# ADC-Z-DOK.net
KiCad netlist of a schematic drawn in Altium Designer
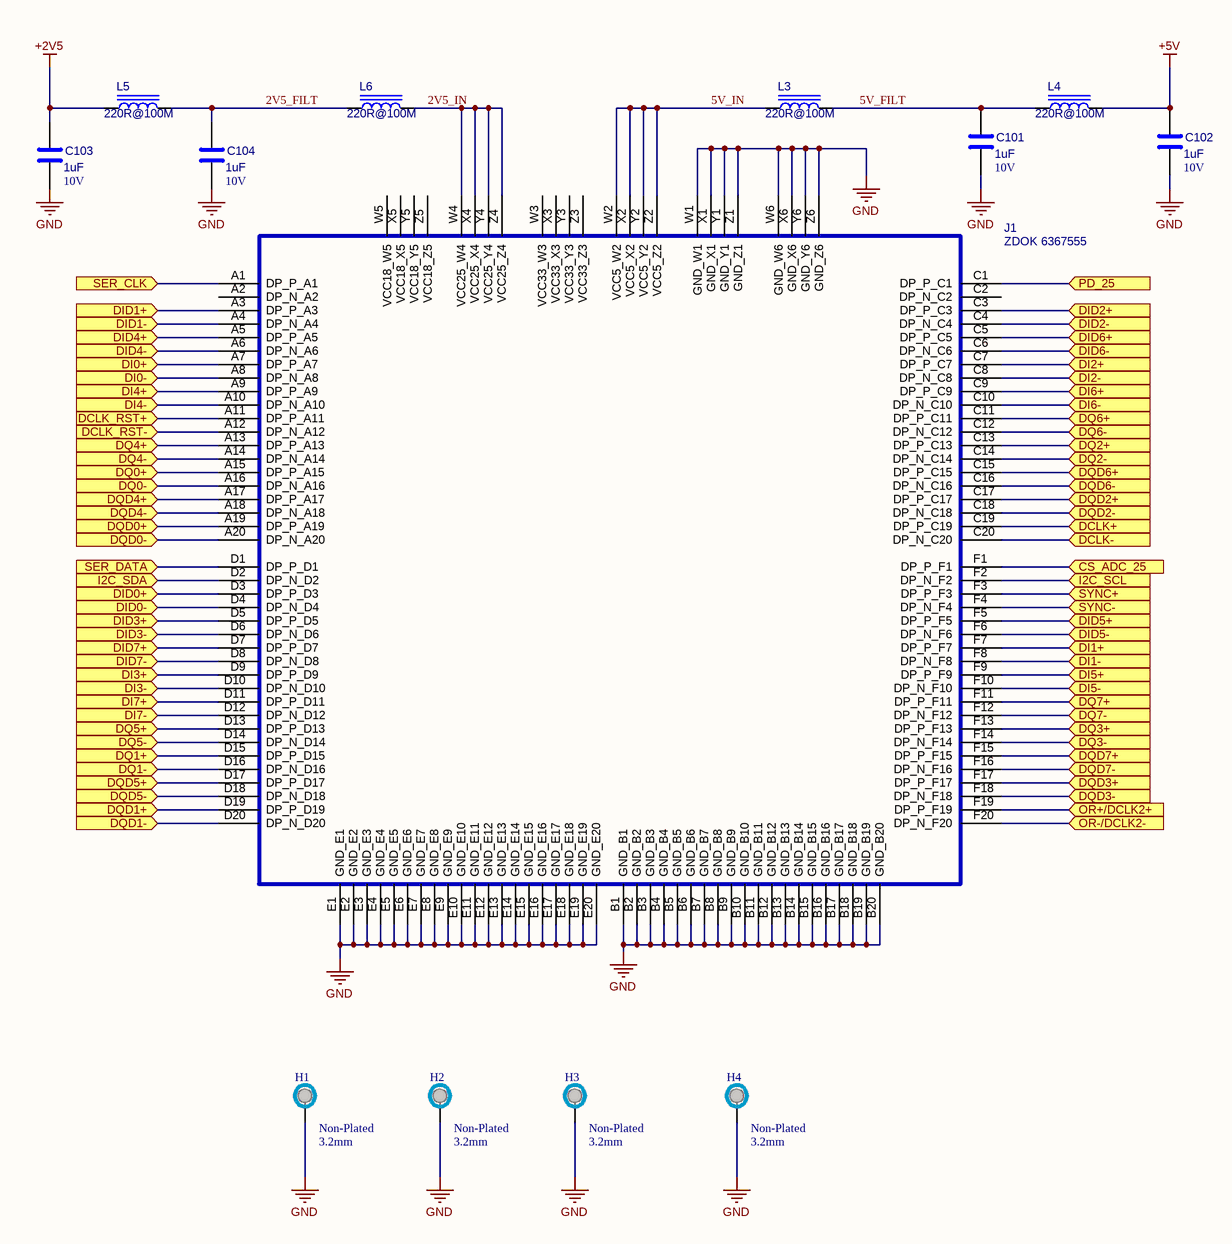
[diagram p0: ADC-Z-DOK.SchDoc]

(export (version "E")
  (design (tool "Eeschema 10.0.6"))
  (components
    (comp (ref "C101")
      (value "1uF")
      (footprint "CAPC1632X80USR")
      (description "CAP SMD 0603")
      (fields (field (name "VOLTAGE") "10V") (field (name "CREATED_BY") "*") (field (name "CHECKED_BY") "*"))
      (libsource (lib "Abdus-TEMP") (part "CAP-0603"))
    )
    (comp (ref "C102")
      (value "1uF")
      (footprint "CAPC1632X80USR")
      (description "CAP SMD 0603")
      (fields (field (name "VOLTAGE") "10V") (field (name "CREATED_BY") "*") (field (name "CHECKED_BY") "*"))
      (libsource (lib "Abdus-TEMP") (part "CAP-0603"))
    )
    (comp (ref "C103")
      (value "1uF")
      (footprint "CAPC1632X80USR")
      (description "CAP SMD 0603")
      (fields (field (name "VOLTAGE") "10V") (field (name "CREATED_BY") "*") (field (name "CHECKED_BY") "*"))
      (libsource (lib "Abdus-TEMP") (part "CAP-0603"))
    )
    (comp (ref "C104")
      (value "1uF")
      (footprint "CAPC1632X80USR")
      (description "CAP SMD 0603")
      (fields (field (name "VOLTAGE") "10V") (field (name "CREATED_BY") "*") (field (name "CHECKED_BY") "*"))
      (libsource (lib "Abdus-TEMP") (part "CAP-0603"))
    )
    (comp (ref "H1")
      (value "Non-Plated")
      (footprint "HOLE")
      (description "PCB Mounting Hole")
      (fields (field (name "HOLEDIA") "3.2mm"))
      (libsource (lib "Analog_Outputs") (part "Unplated Hole_3.2mm"))
    )
    (comp (ref "H2")
      (value "Non-Plated")
      (footprint "HOLE")
      (description "PCB Mounting Hole")
      (fields (field (name "HOLEDIA") "3.2mm"))
      (libsource (lib "Analog_Outputs") (part "Unplated Hole_3.2mm"))
    )
    (comp (ref "H3")
      (value "Non-Plated")
      (footprint "HOLE")
      (description "PCB Mounting Hole")
      (fields (field (name "HOLEDIA") "3.2mm"))
      (libsource (lib "Analog_Outputs") (part "Unplated Hole_3.2mm"))
    )
    (comp (ref "H4")
      (value "Non-Plated")
      (footprint "HOLE")
      (description "PCB Mounting Hole")
      (fields (field (name "HOLEDIA") "3.2mm"))
      (libsource (lib "Analog_Outputs") (part "Unplated Hole_3.2mm"))
    )
    (comp (ref "J1")
      (value "Z-DOK")
      (footprint "TYCO6367555")
      (fields
        (field (name "MANUFACTURER_PN") "ZDOK 6367555")
        (field (name "CREATED_BY") "CT")
        (field (name "CHECKED_BY") "*")
      )
      (libsource (lib "Charles-TEMP") (part "ZDOK 6367555"))
    )
    (comp (ref "L3")
      (value "TDK")
      (footprint "INDC1608X80USR")
      (description "POWER LINE")
      (fields
        (field (name "VOLTAGE") "220R@100M")
        (field (name "CREATED_BY") "*")
        (field (name "CHECKED_BY") "*")
      )
      (libsource (lib "Charles-TEMP") (part "MPZ16085221A"))
    )
    (comp (ref "L4")
      (value "TDK")
      (footprint "INDC1608X80USR")
      (description "POWER LINE")
      (fields
        (field (name "VOLTAGE") "220R@100M")
        (field (name "CREATED_BY") "*")
        (field (name "CHECKED_BY") "*")
      )
      (libsource (lib "Charles-TEMP") (part "MPZ16085221A"))
    )
    (comp (ref "L5")
      (value "TDK")
      (footprint "INDC1608X80USR")
      (description "POWER LINE")
      (fields
        (field (name "VOLTAGE") "220R@100M")
        (field (name "CREATED_BY") "*")
        (field (name "CHECKED_BY") "*")
      )
      (libsource (lib "Charles-TEMP") (part "MPZ16085221A"))
    )
    (comp (ref "L6")
      (value "TDK")
      (footprint "INDC1608X80USR")
      (description "POWER LINE")
      (fields
        (field (name "VOLTAGE") "220R@100M")
        (field (name "CREATED_BY") "*")
        (field (name "CHECKED_BY") "*")
      )
      (libsource (lib "Charles-TEMP") (part "MPZ16085221A"))
    )
  )
  (nets
    (net (code "1") (name "+2V5") (class "Default")
      (node (ref "C103") (pin "1") (pinfunction "1_1") (pintype "passive"))
      (node (ref "L5") (pin "1") (pinfunction "1_1") (pintype "passive"))
    )
    (net (code "2") (name "+5V") (class "Default")
      (node (ref "C102") (pin "1") (pinfunction "1_1") (pintype "passive"))
      (node (ref "L4") (pin "2") (pinfunction "2_2") (pintype "passive"))
    )
    (net (code "3") (name "/2V5_FILT") (class "Default")
      (node (ref "C104") (pin "1") (pinfunction "1_1") (pintype "passive"))
      (node (ref "L5") (pin "2") (pinfunction "2_2") (pintype "passive"))
      (node (ref "L6") (pin "1") (pinfunction "1_1") (pintype "passive"))
    )
    (net (code "4") (name "/2V5_IN") (class "Default")
      (node (ref "J1") (pin "W4") (pinfunction "VCC25_W4_W4") (pintype "power_in"))
      (node (ref "J1") (pin "X4") (pinfunction "VCC25_X4_X4") (pintype "power_in"))
      (node (ref "J1") (pin "Y4") (pinfunction "VCC25_Y4_Y4") (pintype "power_in"))
      (node (ref "J1") (pin "Z4") (pinfunction "VCC25_Z4_Z4") (pintype "power_in"))
      (node (ref "L6") (pin "2") (pinfunction "2_2") (pintype "passive"))
    )
    (net (code "5") (name "/5V_FILT") (class "Default")
      (node (ref "C101") (pin "1") (pinfunction "1_1") (pintype "passive"))
      (node (ref "L3") (pin "2") (pinfunction "2_2") (pintype "passive"))
      (node (ref "L4") (pin "1") (pinfunction "1_1") (pintype "passive"))
    )
    (net (code "6") (name "/5V_IN") (class "Default")
      (node (ref "J1") (pin "W2") (pinfunction "VCC5_W2_W2") (pintype "power_in"))
      (node (ref "J1") (pin "X2") (pinfunction "VCC5_X2_X2") (pintype "power_in"))
      (node (ref "J1") (pin "Y2") (pinfunction "VCC5_Y2_Y2") (pintype "power_in"))
      (node (ref "J1") (pin "Z2") (pinfunction "VCC5_Z2_Z2") (pintype "power_in"))
      (node (ref "L3") (pin "1") (pinfunction "1_1") (pintype "passive"))
    )
    (net (code "7") (name "/CS_ADC_25") (class "Default")
      (node (ref "J1") (pin "F1") (pinfunction "DP_P_F1_F1") (pintype "passive"))
    )
    (net (code "8") (name "/DCLK+") (class "Default")
      (node (ref "J1") (pin "C19") (pinfunction "DP_P_C19_C19") (pintype "passive"))
    )
    (net (code "9") (name "/DCLK-") (class "Default")
      (node (ref "J1") (pin "C20") (pinfunction "DP_N_C20_C20") (pintype "passive"))
    )
    (net (code "10") (name "/DCLK_RST+") (class "Default")
      (node (ref "J1") (pin "A11") (pinfunction "DP_P_A11_A11") (pintype "passive"))
    )
    (net (code "11") (name "/DCLK_RST-") (class "Default")
      (node (ref "J1") (pin "A12") (pinfunction "DP_N_A12_A12") (pintype "passive"))
    )
    (net (code "12") (name "/DI0+") (class "Default")
      (node (ref "J1") (pin "A7") (pinfunction "DP_P_A7_A7") (pintype "passive"))
    )
    (net (code "13") (name "/DI0-") (class "Default")
      (node (ref "J1") (pin "A8") (pinfunction "DP_N_A8_A8") (pintype "passive"))
    )
    (net (code "14") (name "/DI1+") (class "Default")
      (node (ref "J1") (pin "F7") (pinfunction "DP_P_F7_F7") (pintype "passive"))
    )
    (net (code "15") (name "/DI1-") (class "Default")
      (node (ref "J1") (pin "F8") (pinfunction "DP_N_F8_F8") (pintype "passive"))
    )
    (net (code "16") (name "/DI2+") (class "Default")
      (node (ref "J1") (pin "C7") (pinfunction "DP_P_C7_C7") (pintype "passive"))
    )
    (net (code "17") (name "/DI2-") (class "Default")
      (node (ref "J1") (pin "C8") (pinfunction "DP_N_C8_C8") (pintype "passive"))
    )
    (net (code "18") (name "/DI3+") (class "Default")
      (node (ref "J1") (pin "D9") (pinfunction "DP_P_D9_D9") (pintype "passive"))
    )
    (net (code "19") (name "/DI3-") (class "Default")
      (node (ref "J1") (pin "D10") (pinfunction "DP_N_D10_D10") (pintype "passive"))
    )
    (net (code "20") (name "/DI4+") (class "Default")
      (node (ref "J1") (pin "A9") (pinfunction "DP_P_A9_A9") (pintype "passive"))
    )
    (net (code "21") (name "/DI4-") (class "Default")
      (node (ref "J1") (pin "A10") (pinfunction "DP_N_A10_A10") (pintype "passive"))
    )
    (net (code "22") (name "/DI5+") (class "Default")
      (node (ref "J1") (pin "F9") (pinfunction "DP_P_F9_F9") (pintype "passive"))
    )
    (net (code "23") (name "/DI5-") (class "Default")
      (node (ref "J1") (pin "F10") (pinfunction "DP_N_F10_F10") (pintype "passive"))
    )
    (net (code "24") (name "/DI6+") (class "Default")
      (node (ref "J1") (pin "C9") (pinfunction "DP_P_C9_C9") (pintype "passive"))
    )
    (net (code "25") (name "/DI6-") (class "Default")
      (node (ref "J1") (pin "C10") (pinfunction "DP_N_C10_C10") (pintype "passive"))
    )
    (net (code "26") (name "/DI7+") (class "Default")
      (node (ref "J1") (pin "D11") (pinfunction "DP_P_D11_D11") (pintype "passive"))
    )
    (net (code "27") (name "/DI7-") (class "Default")
      (node (ref "J1") (pin "D12") (pinfunction "DP_N_D12_D12") (pintype "passive"))
    )
    (net (code "28") (name "/DID0+") (class "Default")
      (node (ref "J1") (pin "D3") (pinfunction "DP_P_D3_D3") (pintype "passive"))
    )
    (net (code "29") (name "/DID0-") (class "Default")
      (node (ref "J1") (pin "D4") (pinfunction "DP_N_D4_D4") (pintype "passive"))
    )
    (net (code "30") (name "/DID1+") (class "Default")
      (node (ref "J1") (pin "A3") (pinfunction "DP_P_A3_A3") (pintype "passive"))
    )
    (net (code "31") (name "/DID1-") (class "Default")
      (node (ref "J1") (pin "A4") (pinfunction "DP_N_A4_A4") (pintype "passive"))
    )
    (net (code "32") (name "/DID2+") (class "Default")
      (node (ref "J1") (pin "C3") (pinfunction "DP_P_C3_C3") (pintype "passive"))
    )
    (net (code "33") (name "/DID2-") (class "Default")
      (node (ref "J1") (pin "C4") (pinfunction "DP_N_C4_C4") (pintype "passive"))
    )
    (net (code "34") (name "/DID3+") (class "Default")
      (node (ref "J1") (pin "D5") (pinfunction "DP_P_D5_D5") (pintype "passive"))
    )
    (net (code "35") (name "/DID3-") (class "Default")
      (node (ref "J1") (pin "D6") (pinfunction "DP_N_D6_D6") (pintype "passive"))
    )
    (net (code "36") (name "/DID4+") (class "Default")
      (node (ref "J1") (pin "A5") (pinfunction "DP_P_A5_A5") (pintype "passive"))
    )
    (net (code "37") (name "/DID4-") (class "Default")
      (node (ref "J1") (pin "A6") (pinfunction "DP_N_A6_A6") (pintype "passive"))
    )
    (net (code "38") (name "/DID5+") (class "Default")
      (node (ref "J1") (pin "F5") (pinfunction "DP_P_F5_F5") (pintype "passive"))
    )
    (net (code "39") (name "/DID5-") (class "Default")
      (node (ref "J1") (pin "F6") (pinfunction "DP_N_F6_F6") (pintype "passive"))
    )
    (net (code "40") (name "/DID6+") (class "Default")
      (node (ref "J1") (pin "C5") (pinfunction "DP_P_C5_C5") (pintype "passive"))
    )
    (net (code "41") (name "/DID6-") (class "Default")
      (node (ref "J1") (pin "C6") (pinfunction "DP_N_C6_C6") (pintype "passive"))
    )
    (net (code "42") (name "/DID7+") (class "Default")
      (node (ref "J1") (pin "D7") (pinfunction "DP_P_D7_D7") (pintype "passive"))
    )
    (net (code "43") (name "/DID7-") (class "Default")
      (node (ref "J1") (pin "D8") (pinfunction "DP_N_D8_D8") (pintype "passive"))
    )
    (net (code "44") (name "/DQ0+") (class "Default")
      (node (ref "J1") (pin "A15") (pinfunction "DP_P_A15_A15") (pintype "passive"))
    )
    (net (code "45") (name "/DQ0-") (class "Default")
      (node (ref "J1") (pin "A16") (pinfunction "DP_N_A16_A16") (pintype "passive"))
    )
    (net (code "46") (name "/DQ1+") (class "Default")
      (node (ref "J1") (pin "D15") (pinfunction "DP_P_D15_D15") (pintype "passive"))
    )
    (net (code "47") (name "/DQ1-") (class "Default")
      (node (ref "J1") (pin "D16") (pinfunction "DP_N_D16_D16") (pintype "passive"))
    )
    (net (code "48") (name "/DQ2+") (class "Default")
      (node (ref "J1") (pin "C13") (pinfunction "DP_P_C13_C13") (pintype "passive"))
    )
    (net (code "49") (name "/DQ2-") (class "Default")
      (node (ref "J1") (pin "C14") (pinfunction "DP_N_C14_C14") (pintype "passive"))
    )
    (net (code "50") (name "/DQ3+") (class "Default")
      (node (ref "J1") (pin "F13") (pinfunction "DP_P_F13_F13") (pintype "passive"))
    )
    (net (code "51") (name "/DQ3-") (class "Default")
      (node (ref "J1") (pin "F14") (pinfunction "DP_N_F14_F14") (pintype "passive"))
    )
    (net (code "52") (name "/DQ4+") (class "Default")
      (node (ref "J1") (pin "A13") (pinfunction "DP_P_A13_A13") (pintype "passive"))
    )
    (net (code "53") (name "/DQ4-") (class "Default")
      (node (ref "J1") (pin "A14") (pinfunction "DP_N_A14_A14") (pintype "passive"))
    )
    (net (code "54") (name "/DQ5+") (class "Default")
      (node (ref "J1") (pin "D13") (pinfunction "DP_P_D13_D13") (pintype "passive"))
    )
    (net (code "55") (name "/DQ5-") (class "Default")
      (node (ref "J1") (pin "D14") (pinfunction "DP_N_D14_D14") (pintype "passive"))
    )
    (net (code "56") (name "/DQ6+") (class "Default")
      (node (ref "J1") (pin "C11") (pinfunction "DP_P_C11_C11") (pintype "passive"))
    )
    (net (code "57") (name "/DQ6-") (class "Default")
      (node (ref "J1") (pin "C12") (pinfunction "DP_N_C12_C12") (pintype "passive"))
    )
    (net (code "58") (name "/DQ7+") (class "Default")
      (node (ref "J1") (pin "F11") (pinfunction "DP_P_F11_F11") (pintype "passive"))
    )
    (net (code "59") (name "/DQ7-") (class "Default")
      (node (ref "J1") (pin "F12") (pinfunction "DP_N_F12_F12") (pintype "passive"))
    )
    (net (code "60") (name "/DQD0+") (class "Default")
      (node (ref "J1") (pin "A19") (pinfunction "DP_P_A19_A19") (pintype "passive"))
    )
    (net (code "61") (name "/DQD0-") (class "Default")
      (node (ref "J1") (pin "A20") (pinfunction "DP_N_A20_A20") (pintype "passive"))
    )
    (net (code "62") (name "/DQD1+") (class "Default")
      (node (ref "J1") (pin "D19") (pinfunction "DP_P_D19_D19") (pintype "passive"))
    )
    (net (code "63") (name "/DQD1-") (class "Default")
      (node (ref "J1") (pin "D20") (pinfunction "DP_N_D20_D20") (pintype "passive"))
    )
    (net (code "64") (name "/DQD2+") (class "Default")
      (node (ref "J1") (pin "C17") (pinfunction "DP_P_C17_C17") (pintype "passive"))
    )
    (net (code "65") (name "/DQD2-") (class "Default")
      (node (ref "J1") (pin "C18") (pinfunction "DP_N_C18_C18") (pintype "passive"))
    )
    (net (code "66") (name "/DQD3+") (class "Default")
      (node (ref "J1") (pin "F17") (pinfunction "DP_P_F17_F17") (pintype "passive"))
    )
    (net (code "67") (name "/DQD3-") (class "Default")
      (node (ref "J1") (pin "F18") (pinfunction "DP_N_F18_F18") (pintype "passive"))
    )
    (net (code "68") (name "/DQD4+") (class "Default")
      (node (ref "J1") (pin "A17") (pinfunction "DP_P_A17_A17") (pintype "passive"))
    )
    (net (code "69") (name "/DQD4-") (class "Default")
      (node (ref "J1") (pin "A18") (pinfunction "DP_N_A18_A18") (pintype "passive"))
    )
    (net (code "70") (name "/DQD5+") (class "Default")
      (node (ref "J1") (pin "D17") (pinfunction "DP_P_D17_D17") (pintype "passive"))
    )
    (net (code "71") (name "/DQD5-") (class "Default")
      (node (ref "J1") (pin "D18") (pinfunction "DP_N_D18_D18") (pintype "passive"))
    )
    (net (code "72") (name "/DQD6+") (class "Default")
      (node (ref "J1") (pin "C15") (pinfunction "DP_P_C15_C15") (pintype "passive"))
    )
    (net (code "73") (name "/DQD6-") (class "Default")
      (node (ref "J1") (pin "C16") (pinfunction "DP_N_C16_C16") (pintype "passive"))
    )
    (net (code "74") (name "/DQD7+") (class "Default")
      (node (ref "J1") (pin "F15") (pinfunction "DP_P_F15_F15") (pintype "passive"))
    )
    (net (code "75") (name "/DQD7-") (class "Default")
      (node (ref "J1") (pin "F16") (pinfunction "DP_N_F16_F16") (pintype "passive"))
    )
    (net (code "76") (name "/I2C_SCL") (class "Default")
      (node (ref "J1") (pin "F2") (pinfunction "DP_N_F2_F2") (pintype "passive"))
    )
    (net (code "77") (name "/I2C_SDA") (class "Default")
      (node (ref "J1") (pin "D2") (pinfunction "DP_N_D2_D2") (pintype "passive"))
    )
    (net (code "78") (name "/OR+{slash}DCLK2+") (class "Default")
      (node (ref "J1") (pin "F19") (pinfunction "DP_P_F19_F19") (pintype "passive"))
    )
    (net (code "79") (name "/OR-{slash}DCLK2-") (class "Default")
      (node (ref "J1") (pin "F20") (pinfunction "DP_N_F20_F20") (pintype "passive"))
    )
    (net (code "80") (name "/PD_25") (class "Default")
      (node (ref "J1") (pin "C1") (pinfunction "DP_P_C1_C1") (pintype "passive"))
    )
    (net (code "81") (name "/SER_CLK") (class "Default")
      (node (ref "J1") (pin "A1") (pinfunction "DP_P_A1_A1") (pintype "passive"))
    )
    (net (code "82") (name "/SER_DATA") (class "Default")
      (node (ref "J1") (pin "D1") (pinfunction "DP_P_D1_D1") (pintype "passive"))
    )
    (net (code "83") (name "/SYNC+") (class "Default")
      (node (ref "J1") (pin "F3") (pinfunction "DP_P_F3_F3") (pintype "passive"))
    )
    (net (code "84") (name "/SYNC-") (class "Default")
      (node (ref "J1") (pin "F4") (pinfunction "DP_N_F4_F4") (pintype "passive"))
    )
    (net (code "85") (name "GND") (class "Default")
      (node (ref "C101") (pin "2") (pinfunction "2_2") (pintype "passive"))
      (node (ref "C102") (pin "2") (pinfunction "2_2") (pintype "passive"))
      (node (ref "C103") (pin "2") (pinfunction "2_2") (pintype "passive"))
      (node (ref "C104") (pin "2") (pinfunction "2_2") (pintype "passive"))
      (node (ref "H1") (pin "1") (pinfunction "TP_1") (pintype "passive"))
      (node (ref "H2") (pin "1") (pinfunction "TP_1") (pintype "passive"))
      (node (ref "H3") (pin "1") (pinfunction "TP_1") (pintype "passive"))
      (node (ref "H4") (pin "1") (pinfunction "TP_1") (pintype "passive"))
      (node (ref "J1") (pin "B1") (pinfunction "GND_B1_B1") (pintype "passive"))
      (node (ref "J1") (pin "B10") (pinfunction "GND_B10_B10") (pintype "passive"))
      (node (ref "J1") (pin "B11") (pinfunction "GND_B11_B11") (pintype "passive"))
      (node (ref "J1") (pin "B12") (pinfunction "GND_B12_B12") (pintype "passive"))
      (node (ref "J1") (pin "B13") (pinfunction "GND_B13_B13") (pintype "passive"))
      (node (ref "J1") (pin "B14") (pinfunction "GND_B14_B14") (pintype "passive"))
      (node (ref "J1") (pin "B15") (pinfunction "GND_B15_B15") (pintype "passive"))
      (node (ref "J1") (pin "B16") (pinfunction "GND_B16_B16") (pintype "passive"))
      (node (ref "J1") (pin "B17") (pinfunction "GND_B17_B17") (pintype "passive"))
      (node (ref "J1") (pin "B18") (pinfunction "GND_B18_B18") (pintype "passive"))
      (node (ref "J1") (pin "B19") (pinfunction "GND_B19_B19") (pintype "passive"))
      (node (ref "J1") (pin "B2") (pinfunction "GND_B2_B2") (pintype "passive"))
      (node (ref "J1") (pin "B20") (pinfunction "GND_B20_B20") (pintype "passive"))
      (node (ref "J1") (pin "B3") (pinfunction "GND_B3_B3") (pintype "passive"))
      (node (ref "J1") (pin "B4") (pinfunction "GND_B4_B4") (pintype "passive"))
      (node (ref "J1") (pin "B5") (pinfunction "GND_B5_B5") (pintype "passive"))
      (node (ref "J1") (pin "B6") (pinfunction "GND_B6_B6") (pintype "passive"))
      (node (ref "J1") (pin "B7") (pinfunction "GND_B7_B7") (pintype "passive"))
      (node (ref "J1") (pin "B8") (pinfunction "GND_B8_B8") (pintype "passive"))
      (node (ref "J1") (pin "B9") (pinfunction "GND_B9_B9") (pintype "passive"))
      (node (ref "J1") (pin "E1") (pinfunction "GND_E1_E1") (pintype "passive"))
      (node (ref "J1") (pin "E10") (pinfunction "GND_E10_E10") (pintype "passive"))
      (node (ref "J1") (pin "E11") (pinfunction "GND_E11_E11") (pintype "passive"))
      (node (ref "J1") (pin "E12") (pinfunction "GND_E12_E12") (pintype "passive"))
      (node (ref "J1") (pin "E13") (pinfunction "GND_E13_E13") (pintype "passive"))
      (node (ref "J1") (pin "E14") (pinfunction "GND_E14_E14") (pintype "passive"))
      (node (ref "J1") (pin "E15") (pinfunction "GND_E15_E15") (pintype "passive"))
      (node (ref "J1") (pin "E16") (pinfunction "GND_E16_E16") (pintype "passive"))
      (node (ref "J1") (pin "E17") (pinfunction "GND_E17_E17") (pintype "passive"))
      (node (ref "J1") (pin "E18") (pinfunction "GND_E18_E18") (pintype "passive"))
      (node (ref "J1") (pin "E19") (pinfunction "GND_E19_E19") (pintype "passive"))
      (node (ref "J1") (pin "E2") (pinfunction "GND_E2_E2") (pintype "passive"))
      (node (ref "J1") (pin "E20") (pinfunction "GND_E20_E20") (pintype "passive"))
      (node (ref "J1") (pin "E3") (pinfunction "GND_E3_E3") (pintype "passive"))
      (node (ref "J1") (pin "E4") (pinfunction "GND_E4_E4") (pintype "passive"))
      (node (ref "J1") (pin "E5") (pinfunction "GND_E5_E5") (pintype "passive"))
      (node (ref "J1") (pin "E6") (pinfunction "GND_E6_E6") (pintype "passive"))
      (node (ref "J1") (pin "E7") (pinfunction "GND_E7_E7") (pintype "passive"))
      (node (ref "J1") (pin "E8") (pinfunction "GND_E8_E8") (pintype "passive"))
      (node (ref "J1") (pin "E9") (pinfunction "GND_E9_E9") (pintype "passive"))
      (node (ref "J1") (pin "W1") (pinfunction "GND_W1_W1") (pintype "passive"))
      (node (ref "J1") (pin "W6") (pinfunction "GND_W6_W6") (pintype "passive"))
      (node (ref "J1") (pin "X1") (pinfunction "GND_X1_X1") (pintype "passive"))
      (node (ref "J1") (pin "X6") (pinfunction "GND_X6_X6") (pintype "passive"))
      (node (ref "J1") (pin "Y1") (pinfunction "GND_Y1_Y1") (pintype "passive"))
      (node (ref "J1") (pin "Y6") (pinfunction "GND_Y6_Y6") (pintype "passive"))
      (node (ref "J1") (pin "Z1") (pinfunction "GND_Z1_Z1") (pintype "passive"))
      (node (ref "J1") (pin "Z6") (pinfunction "GND_Z6_Z6") (pintype "passive"))
    )
    (net (code "86") (name "unconnected-(J1-DP_N_A2-PadA2)") (class "Default")
      (node (ref "J1") (pin "A2") (pinfunction "DP_N_A2_A2") (pintype "passive"))
    )
    (net (code "87") (name "unconnected-(J1-DP_N_C2-PadC2)") (class "Default")
      (node (ref "J1") (pin "C2") (pinfunction "DP_N_C2_C2") (pintype "passive"))
    )
    (net (code "88") (name "unconnected-(J1-VCC18_W5-PadW5)") (class "Default")
      (node (ref "J1") (pin "W5") (pinfunction "VCC18_W5_W5") (pintype "power_in"))
    )
    (net (code "89") (name "unconnected-(J1-VCC18_X5-PadX5)") (class "Default")
      (node (ref "J1") (pin "X5") (pinfunction "VCC18_X5_X5") (pintype "power_in"))
    )
    (net (code "90") (name "unconnected-(J1-VCC18_Y5-PadY5)") (class "Default")
      (node (ref "J1") (pin "Y5") (pinfunction "VCC18_Y5_Y5") (pintype "power_in"))
    )
    (net (code "91") (name "unconnected-(J1-VCC18_Z5-PadZ5)") (class "Default")
      (node (ref "J1") (pin "Z5") (pinfunction "VCC18_Z5_Z5") (pintype "power_in"))
    )
    (net (code "92") (name "unconnected-(J1-VCC33_W3-PadW3)") (class "Default")
      (node (ref "J1") (pin "W3") (pinfunction "VCC33_W3_W3") (pintype "power_in"))
    )
    (net (code "93") (name "unconnected-(J1-VCC33_X3-PadX3)") (class "Default")
      (node (ref "J1") (pin "X3") (pinfunction "VCC33_X3_X3") (pintype "power_in"))
    )
    (net (code "94") (name "unconnected-(J1-VCC33_Y3-PadY3)") (class "Default")
      (node (ref "J1") (pin "Y3") (pinfunction "VCC33_Y3_Y3") (pintype "power_in"))
    )
    (net (code "95") (name "unconnected-(J1-VCC33_Z3-PadZ3)") (class "Default")
      (node (ref "J1") (pin "Z3") (pinfunction "VCC33_Z3_Z3") (pintype "power_in"))
    )
  )
)
